# SCH_ESP32.net
KiCad netlist of a schematic drawn in EasyEDA
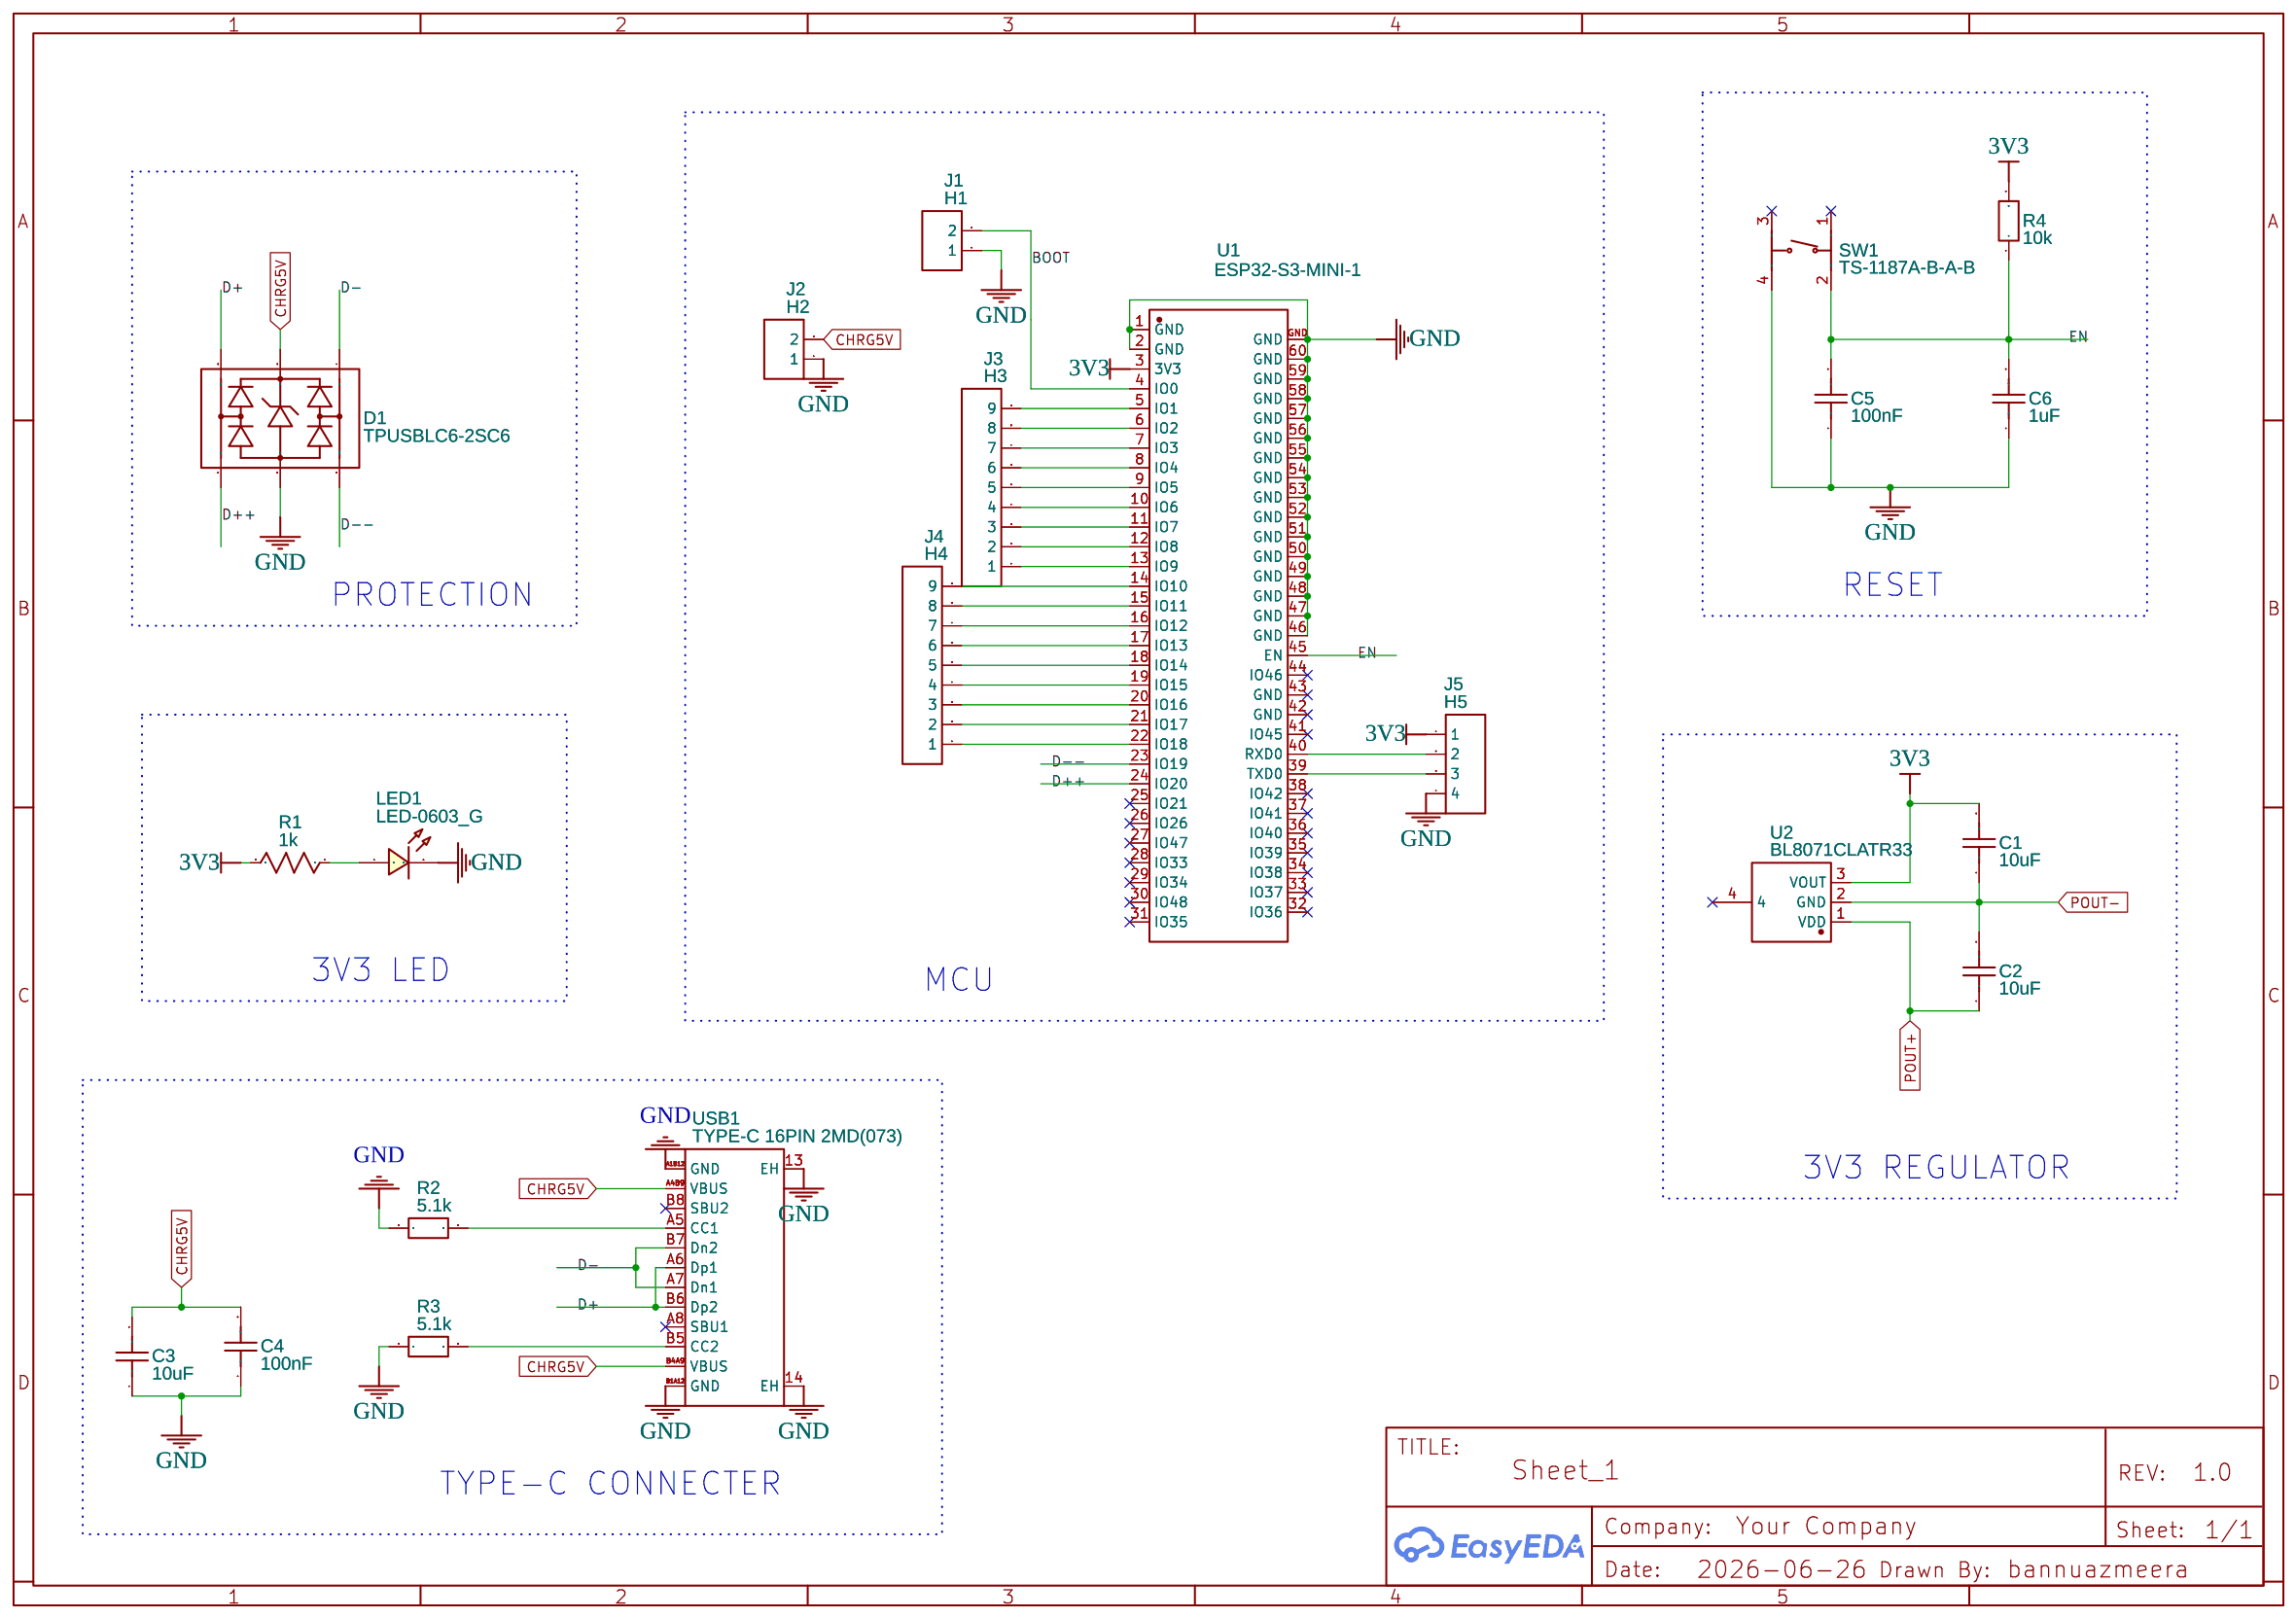
[diagram p0: schematic sheet]

(export (version "E")
  (design (tool "Eeschema 10.0.6"))
  (components
    (comp (ref "C1") (value "10uF") (libsource (lib "") (part "C_0603_US")))
    (comp (ref "C2") (value "10uF") (libsource (lib "") (part "C_0603_US")))
    (comp (ref "C3") (value "10uF") (libsource (lib "") (part "C_0603_US")))
    (comp (ref "C4") (value "100nF") (libsource (lib "") (part "C_0603_US")))
    (comp (ref "C5") (value "100nF") (libsource (lib "") (part "C_0603_US")))
    (comp (ref "C6") (value "1uF") (libsource (lib "") (part "C_0603_US")))
    (comp (ref "D1")
      (value "TPUSBLC6-2SC6")
      (fields (field (name "Manufacturer") "TECH PUBLIC(台舟)"))
      (libsource (lib "") (part "TPUSBLC6-2SC6"))
    )
    (comp (ref "J1") (value "H1") (libsource (lib "") (part "HDR-M-2.54_1x2")))
    (comp (ref "J2") (value "H2") (libsource (lib "") (part "HDR-M-2.54_1x2")))
    (comp (ref "J3") (value "H3") (libsource (lib "") (part "HDR-M-2.54_1x9")))
    (comp (ref "J4") (value "H4") (libsource (lib "") (part "HDR-M-2.54_1x9")))
    (comp (ref "J5") (value "H5") (libsource (lib "") (part "HDR-M-2.54_1x4")))
    (comp (ref "LED1")
      (value "LED-0603_G")
      (fields
        (field (name "Manufacturer Part") "19-217/GHC-YR1S2/3T")
        (field (name "Manufacturer") "EVERLIGHT(台湾亿光)")
      )
      (libsource (lib "") (part "LED-0603_G"))
    )
    (comp (ref "R1") (value "1k") (libsource (lib "") (part "R_0603_US")))
    (comp (ref "R2") (value "5.1k") (libsource (lib "") (part "R_0603_EU")))
    (comp (ref "R3") (value "5.1k") (libsource (lib "") (part "R_0603_EU")))
    (comp (ref "R4") (value "10k") (libsource (lib "") (part "R_0603_EU_1")))
    (comp (ref "SW1")
      (value "TS-1187A-B-A-B")
      (fields (field (name "Manufacturer") "XKB Connection(中国星坤)"))
      (libsource (lib "") (part "TS-1187A-B-A-B"))
    )
    (comp (ref "U1") (value "ESP32-S3-MINI-1") (libsource (lib "") (part "ESP32-S3-MINI-1")))
    (comp (ref "U2")
      (value "BL8071CLATR33")
      (fields (field (name "Manufacturer") "BL(上海贝岭)"))
      (libsource (lib "") (part "BL8071CLATR33"))
    )
    (comp (ref "USB1")
      (value "TYPE-C 16PIN 2MD(073)")
      (fields (field (name "Manufacturer") "SHOU HAN(首韩)"))
      (libsource (lib "") (part "TYPE-C 16PIN 2MD(073)"))
    )
  )
  (nets
    (net (code "1") (name "/BOOT") (class "Default")
      (node (ref "J1") (pin "2") (pinfunction "2_2") (pintype "unspecified"))
      (node (ref "U1") (pin "4") (pinfunction "IO0_4") (pintype "unspecified"))
    )
    (net (code "2") (name "/D+") (class "Default")
      (node (ref "D1") (pin "6") (pinfunction "I/O1_6") (pintype "unspecified"))
      (node (ref "USB1") (pin "A6") (pinfunction "Dp1_A6") (pintype "unspecified"))
      (node (ref "USB1") (pin "B6") (pinfunction "Dp2_B6") (pintype "unspecified"))
    )
    (net (code "3") (name "/D++") (class "Default")
      (node (ref "D1") (pin "1") (pinfunction "I/O1_1") (pintype "unspecified"))
      (node (ref "U1") (pin "24") (pinfunction "IO20_24") (pintype "unspecified"))
    )
    (net (code "4") (name "/D-") (class "Default")
      (node (ref "D1") (pin "4") (pinfunction "I/O2_4") (pintype "unspecified"))
      (node (ref "USB1") (pin "A7") (pinfunction "Dn1_A7") (pintype "unspecified"))
      (node (ref "USB1") (pin "B7") (pinfunction "Dn2_B7") (pintype "unspecified"))
    )
    (net (code "5") (name "/D--") (class "Default")
      (node (ref "D1") (pin "3") (pinfunction "I/O2_3") (pintype "unspecified"))
      (node (ref "U1") (pin "23") (pinfunction "IO19_23") (pintype "unspecified"))
    )
    (net (code "6") (name "/EN") (class "Default")
      (node (ref "C5") (pin "2") (pinfunction "2_2") (pintype "unspecified"))
      (node (ref "C6") (pin "2") (pinfunction "2_2") (pintype "unspecified"))
      (node (ref "R4") (pin "1") (pinfunction "1_1") (pintype "unspecified"))
      (node (ref "SW1") (pin "2") (pinfunction "B_2") (pintype "unspecified"))
      (node (ref "U1") (pin "45") (pinfunction "EN_45") (pintype "unspecified"))
    )
    (net (code "7") (name "3V3") (class "Default")
      (node (ref "C1") (pin "2") (pinfunction "2_2") (pintype "unspecified"))
      (node (ref "J5") (pin "1") (pinfunction "1_1") (pintype "unspecified"))
      (node (ref "R1") (pin "2") (pinfunction "2_2") (pintype "unspecified"))
      (node (ref "R4") (pin "2") (pinfunction "2_2") (pintype "unspecified"))
      (node (ref "U1") (pin "3") (pinfunction "3V3_3") (pintype "unspecified"))
      (node (ref "U2") (pin "3") (pinfunction "VOUT_3") (pintype "unspecified"))
    )
    (net (code "8") (name "CHRG5V") (class "Default")
      (node (ref "C3") (pin "2") (pinfunction "2_2") (pintype "unspecified"))
      (node (ref "C4") (pin "2") (pinfunction "2_2") (pintype "unspecified"))
      (node (ref "D1") (pin "5") (pinfunction "VBUS_5") (pintype "unspecified"))
      (node (ref "J2") (pin "2") (pinfunction "2_2") (pintype "unspecified"))
      (node (ref "USB1") (pin "A4B9") (pinfunction "VBUS_A4B9") (pintype "unspecified"))
      (node (ref "USB1") (pin "B4A9") (pinfunction "VBUS_B4A9") (pintype "unspecified"))
    )
    (net (code "9") (name "GND") (class "Default")
      (node (ref "C3") (pin "1") (pinfunction "1_1") (pintype "unspecified"))
      (node (ref "C4") (pin "1") (pinfunction "1_1") (pintype "unspecified"))
      (node (ref "C5") (pin "1") (pinfunction "1_1") (pintype "unspecified"))
      (node (ref "C6") (pin "1") (pinfunction "1_1") (pintype "unspecified"))
      (node (ref "D1") (pin "2") (pinfunction "GND_2") (pintype "unspecified"))
      (node (ref "J1") (pin "1") (pinfunction "1_1") (pintype "unspecified"))
      (node (ref "J2") (pin "1") (pinfunction "1_1") (pintype "unspecified"))
      (node (ref "J5") (pin "4") (pinfunction "4_4") (pintype "unspecified"))
      (node (ref "LED1") (pin "2") (pinfunction "2_2") (pintype "unspecified"))
      (node (ref "R2") (pin "1") (pinfunction "1_1") (pintype "unspecified"))
      (node (ref "R3") (pin "1") (pinfunction "1_1") (pintype "unspecified"))
      (node (ref "SW1") (pin "4") (pinfunction "D_4") (pintype "unspecified"))
      (node (ref "U1") (pin "1") (pinfunction "GND_1") (pintype "unspecified"))
      (node (ref "U1") (pin "2") (pinfunction "GND_2") (pintype "unspecified"))
      (node (ref "U1") (pin "46") (pinfunction "GND_46") (pintype "unspecified"))
      (node (ref "U1") (pin "47") (pinfunction "GND_47") (pintype "unspecified"))
      (node (ref "U1") (pin "48") (pinfunction "GND_48") (pintype "unspecified"))
      (node (ref "U1") (pin "49") (pinfunction "GND_49") (pintype "unspecified"))
      (node (ref "U1") (pin "50") (pinfunction "GND_50") (pintype "unspecified"))
      (node (ref "U1") (pin "51") (pinfunction "GND_51") (pintype "unspecified"))
      (node (ref "U1") (pin "52") (pinfunction "GND_52") (pintype "unspecified"))
      (node (ref "U1") (pin "53") (pinfunction "GND_53") (pintype "unspecified"))
      (node (ref "U1") (pin "54") (pinfunction "GND_54") (pintype "unspecified"))
      (node (ref "U1") (pin "55") (pinfunction "GND_55") (pintype "unspecified"))
      (node (ref "U1") (pin "56") (pinfunction "GND_56") (pintype "unspecified"))
      (node (ref "U1") (pin "57") (pinfunction "GND_57") (pintype "unspecified"))
      (node (ref "U1") (pin "58") (pinfunction "GND_58") (pintype "unspecified"))
      (node (ref "U1") (pin "59") (pinfunction "GND_59") (pintype "unspecified"))
      (node (ref "U1") (pin "60") (pinfunction "GND_60") (pintype "unspecified"))
      (node (ref "U1") (pin "GND") (pinfunction "GND_GND") (pintype "unspecified"))
      (node (ref "USB1") (pin "13") (pinfunction "EH_13") (pintype "unspecified"))
      (node (ref "USB1") (pin "14") (pinfunction "EH_14") (pintype "unspecified"))
      (node (ref "USB1") (pin "A1B12") (pinfunction "GND_A1B12") (pintype "unspecified"))
      (node (ref "USB1") (pin "B1A12") (pinfunction "GND_B1A12") (pintype "unspecified"))
    )
    (net (code "10") (name "Net-(LED1-Pad1)") (class "Default")
      (node (ref "LED1") (pin "1") (pinfunction "1_1") (pintype "unspecified"))
      (node (ref "R1") (pin "1") (pinfunction "1_1") (pintype "unspecified"))
    )
    (net (code "11") (name "Net-(U1-IO1)") (class "Default")
      (node (ref "J3") (pin "9") (pinfunction "9_9") (pintype "unspecified"))
      (node (ref "U1") (pin "5") (pinfunction "IO1_5") (pintype "unspecified"))
    )
    (net (code "12") (name "Net-(U1-IO2)") (class "Default")
      (node (ref "J3") (pin "8") (pinfunction "8_8") (pintype "unspecified"))
      (node (ref "U1") (pin "6") (pinfunction "IO2_6") (pintype "unspecified"))
    )
    (net (code "13") (name "Net-(U1-IO3)") (class "Default")
      (node (ref "J3") (pin "7") (pinfunction "7_7") (pintype "unspecified"))
      (node (ref "U1") (pin "7") (pinfunction "IO3_7") (pintype "unspecified"))
    )
    (net (code "14") (name "Net-(U1-IO4)") (class "Default")
      (node (ref "J3") (pin "6") (pinfunction "6_6") (pintype "unspecified"))
      (node (ref "U1") (pin "8") (pinfunction "IO4_8") (pintype "unspecified"))
    )
    (net (code "15") (name "Net-(U1-IO5)") (class "Default")
      (node (ref "J3") (pin "5") (pinfunction "5_5") (pintype "unspecified"))
      (node (ref "U1") (pin "9") (pinfunction "IO5_9") (pintype "unspecified"))
    )
    (net (code "16") (name "Net-(U1-IO6)") (class "Default")
      (node (ref "J3") (pin "4") (pinfunction "4_4") (pintype "unspecified"))
      (node (ref "U1") (pin "10") (pinfunction "IO6_10") (pintype "unspecified"))
    )
    (net (code "17") (name "Net-(U1-IO7)") (class "Default")
      (node (ref "J3") (pin "3") (pinfunction "3_3") (pintype "unspecified"))
      (node (ref "U1") (pin "11") (pinfunction "IO7_11") (pintype "unspecified"))
    )
    (net (code "18") (name "Net-(U1-IO8)") (class "Default")
      (node (ref "J3") (pin "2") (pinfunction "2_2") (pintype "unspecified"))
      (node (ref "U1") (pin "12") (pinfunction "IO8_12") (pintype "unspecified"))
    )
    (net (code "19") (name "Net-(U1-IO9)") (class "Default")
      (node (ref "J3") (pin "1") (pinfunction "1_1") (pintype "unspecified"))
      (node (ref "U1") (pin "13") (pinfunction "IO9_13") (pintype "unspecified"))
    )
    (net (code "20") (name "Net-(U1-IO10)") (class "Default")
      (node (ref "J4") (pin "9") (pinfunction "9_9") (pintype "unspecified"))
      (node (ref "U1") (pin "14") (pinfunction "IO10_14") (pintype "unspecified"))
    )
    (net (code "21") (name "Net-(U1-IO11)") (class "Default")
      (node (ref "J4") (pin "8") (pinfunction "8_8") (pintype "unspecified"))
      (node (ref "U1") (pin "15") (pinfunction "IO11_15") (pintype "unspecified"))
    )
    (net (code "22") (name "Net-(U1-IO12)") (class "Default")
      (node (ref "J4") (pin "7") (pinfunction "7_7") (pintype "unspecified"))
      (node (ref "U1") (pin "16") (pinfunction "IO12_16") (pintype "unspecified"))
    )
    (net (code "23") (name "Net-(U1-IO13)") (class "Default")
      (node (ref "J4") (pin "6") (pinfunction "6_6") (pintype "unspecified"))
      (node (ref "U1") (pin "17") (pinfunction "IO13_17") (pintype "unspecified"))
    )
    (net (code "24") (name "Net-(U1-IO14)") (class "Default")
      (node (ref "J4") (pin "5") (pinfunction "5_5") (pintype "unspecified"))
      (node (ref "U1") (pin "18") (pinfunction "IO14_18") (pintype "unspecified"))
    )
    (net (code "25") (name "Net-(U1-IO15)") (class "Default")
      (node (ref "J4") (pin "4") (pinfunction "4_4") (pintype "unspecified"))
      (node (ref "U1") (pin "19") (pinfunction "IO15_19") (pintype "unspecified"))
    )
    (net (code "26") (name "Net-(U1-IO16)") (class "Default")
      (node (ref "J4") (pin "3") (pinfunction "3_3") (pintype "unspecified"))
      (node (ref "U1") (pin "20") (pinfunction "IO16_20") (pintype "unspecified"))
    )
    (net (code "27") (name "Net-(U1-IO17)") (class "Default")
      (node (ref "J4") (pin "2") (pinfunction "2_2") (pintype "unspecified"))
      (node (ref "U1") (pin "21") (pinfunction "IO17_21") (pintype "unspecified"))
    )
    (net (code "28") (name "Net-(U1-IO18)") (class "Default")
      (node (ref "J4") (pin "1") (pinfunction "1_1") (pintype "unspecified"))
      (node (ref "U1") (pin "22") (pinfunction "IO18_22") (pintype "unspecified"))
    )
    (net (code "29") (name "Net-(U1-RXD0)") (class "Default")
      (node (ref "J5") (pin "2") (pinfunction "2_2") (pintype "unspecified"))
      (node (ref "U1") (pin "40") (pinfunction "RXD0_40") (pintype "unspecified"))
    )
    (net (code "30") (name "Net-(U1-TXD0)") (class "Default")
      (node (ref "J5") (pin "3") (pinfunction "3_3") (pintype "unspecified"))
      (node (ref "U1") (pin "39") (pinfunction "TXD0_39") (pintype "unspecified"))
    )
    (net (code "31") (name "Net-(USB1-CC1)") (class "Default")
      (node (ref "R2") (pin "2") (pinfunction "2_2") (pintype "unspecified"))
      (node (ref "USB1") (pin "A5") (pinfunction "CC1_A5") (pintype "unspecified"))
    )
    (net (code "32") (name "Net-(USB1-CC2)") (class "Default")
      (node (ref "R3") (pin "2") (pinfunction "2_2") (pintype "unspecified"))
      (node (ref "USB1") (pin "B5") (pinfunction "CC2_B5") (pintype "unspecified"))
    )
    (net (code "33") (name "POUT+") (class "Default")
      (node (ref "C2") (pin "1") (pinfunction "1_1") (pintype "unspecified"))
      (node (ref "U2") (pin "1") (pinfunction "VDD_1") (pintype "unspecified"))
    )
    (net (code "34") (name "POUT-") (class "Default")
      (node (ref "C1") (pin "1") (pinfunction "1_1") (pintype "unspecified"))
      (node (ref "C2") (pin "2") (pinfunction "2_2") (pintype "unspecified"))
      (node (ref "U2") (pin "2") (pinfunction "GND_2") (pintype "unspecified"))
    )
    (net (code "35") (name "unconnected-(SW1-A-Pad1)") (class "Default")
      (node (ref "SW1") (pin "1") (pinfunction "A_1") (pintype "unspecified+no_connect"))
    )
    (net (code "36") (name "unconnected-(SW1-C-Pad3)") (class "Default")
      (node (ref "SW1") (pin "3") (pinfunction "C_3") (pintype "unspecified+no_connect"))
    )
    (net (code "37") (name "unconnected-(U1-GND-Pad42)") (class "Default")
      (node (ref "U1") (pin "42") (pinfunction "GND_42") (pintype "unspecified+no_connect"))
    )
    (net (code "38") (name "unconnected-(U1-GND-Pad43)") (class "Default")
      (node (ref "U1") (pin "43") (pinfunction "GND_43") (pintype "unspecified+no_connect"))
    )
    (net (code "39") (name "unconnected-(U1-IO21-Pad25)") (class "Default")
      (node (ref "U1") (pin "25") (pinfunction "IO21_25") (pintype "unspecified+no_connect"))
    )
    (net (code "40") (name "unconnected-(U1-IO26-Pad26)") (class "Default")
      (node (ref "U1") (pin "26") (pinfunction "IO26_26") (pintype "unspecified+no_connect"))
    )
    (net (code "41") (name "unconnected-(U1-IO33-Pad28)") (class "Default")
      (node (ref "U1") (pin "28") (pinfunction "IO33_28") (pintype "unspecified+no_connect"))
    )
    (net (code "42") (name "unconnected-(U1-IO34-Pad29)") (class "Default")
      (node (ref "U1") (pin "29") (pinfunction "IO34_29") (pintype "unspecified+no_connect"))
    )
    (net (code "43") (name "unconnected-(U1-IO35-Pad31)") (class "Default")
      (node (ref "U1") (pin "31") (pinfunction "IO35_31") (pintype "unspecified+no_connect"))
    )
    (net (code "44") (name "unconnected-(U1-IO36-Pad32)") (class "Default")
      (node (ref "U1") (pin "32") (pinfunction "IO36_32") (pintype "unspecified+no_connect"))
    )
    (net (code "45") (name "unconnected-(U1-IO37-Pad33)") (class "Default")
      (node (ref "U1") (pin "33") (pinfunction "IO37_33") (pintype "unspecified+no_connect"))
    )
    (net (code "46") (name "unconnected-(U1-IO38-Pad34)") (class "Default")
      (node (ref "U1") (pin "34") (pinfunction "IO38_34") (pintype "unspecified+no_connect"))
    )
    (net (code "47") (name "unconnected-(U1-IO39-Pad35)") (class "Default")
      (node (ref "U1") (pin "35") (pinfunction "IO39_35") (pintype "unspecified+no_connect"))
    )
    (net (code "48") (name "unconnected-(U1-IO40-Pad36)") (class "Default")
      (node (ref "U1") (pin "36") (pinfunction "IO40_36") (pintype "unspecified+no_connect"))
    )
    (net (code "49") (name "unconnected-(U1-IO41-Pad37)") (class "Default")
      (node (ref "U1") (pin "37") (pinfunction "IO41_37") (pintype "unspecified+no_connect"))
    )
    (net (code "50") (name "unconnected-(U1-IO42-Pad38)") (class "Default")
      (node (ref "U1") (pin "38") (pinfunction "IO42_38") (pintype "unspecified+no_connect"))
    )
    (net (code "51") (name "unconnected-(U1-IO45-Pad41)") (class "Default")
      (node (ref "U1") (pin "41") (pinfunction "IO45_41") (pintype "unspecified+no_connect"))
    )
    (net (code "52") (name "unconnected-(U1-IO46-Pad44)") (class "Default")
      (node (ref "U1") (pin "44") (pinfunction "IO46_44") (pintype "unspecified+no_connect"))
    )
    (net (code "53") (name "unconnected-(U1-IO47-Pad27)") (class "Default")
      (node (ref "U1") (pin "27") (pinfunction "IO47_27") (pintype "unspecified+no_connect"))
    )
    (net (code "54") (name "unconnected-(U1-IO48-Pad30)") (class "Default")
      (node (ref "U1") (pin "30") (pinfunction "IO48_30") (pintype "unspecified+no_connect"))
    )
    (net (code "55") (name "unconnected-(U2-Pad4)") (class "Default")
      (node (ref "U2") (pin "4") (pinfunction "4_4") (pintype "unspecified+no_connect"))
    )
    (net (code "56") (name "unconnected-(USB1-SBU1-PadA8)") (class "Default")
      (node (ref "USB1") (pin "A8") (pinfunction "SBU1_A8") (pintype "unspecified+no_connect"))
    )
    (net (code "57") (name "unconnected-(USB1-SBU2-PadB8)") (class "Default")
      (node (ref "USB1") (pin "B8") (pinfunction "SBU2_B8") (pintype "unspecified+no_connect"))
    )
  )
)
